# Top.net
KiCad netlist of a schematic drawn in Altium Designer
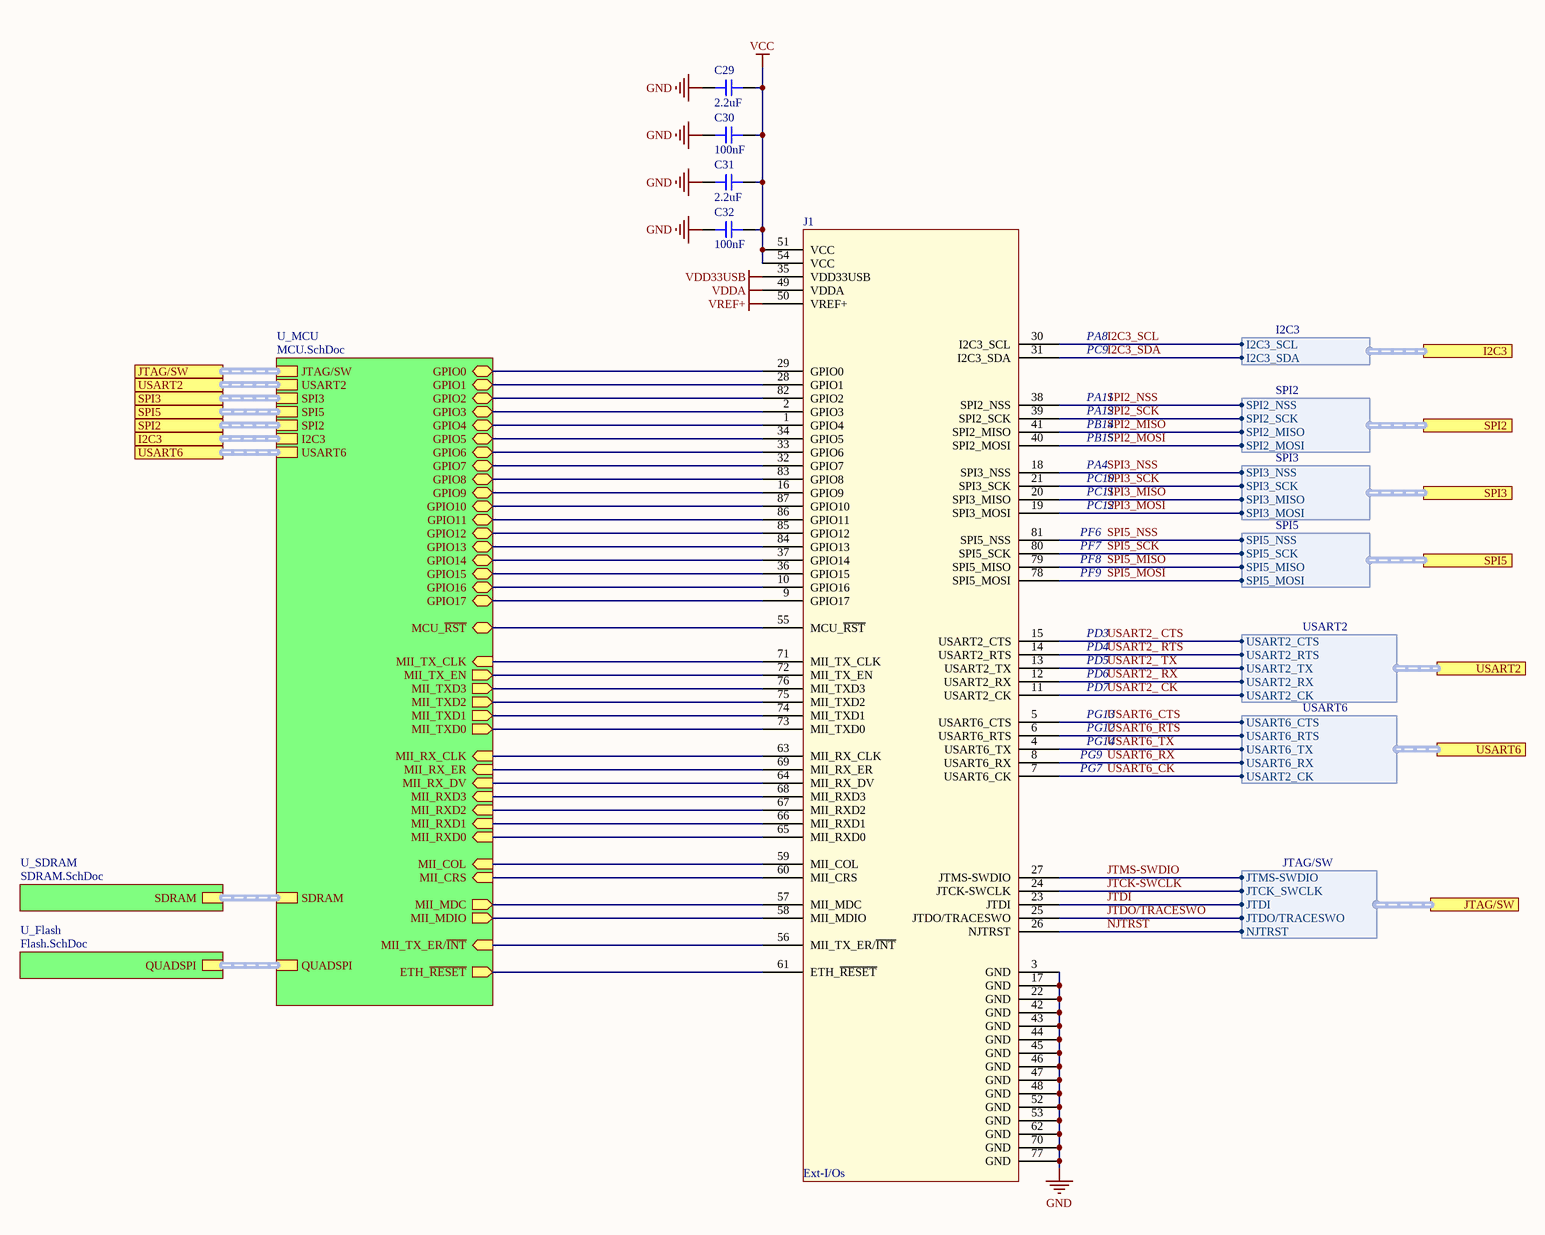
[diagram p0: Top.SchDoc]

(export (version "E")
  (design (tool "Eeschema 10.0.6"))
  (components
    (comp (ref "C29")
      (value "2.2uF")
      (footprint "Capacitor-0603")
      (fields (field (name "Comment") "C-2.2uF-0603"))
      (libsource (lib "Components") (part "C-2.2uF-0603"))
    )
    (comp (ref "C30")
      (value "100nF")
      (footprint "Capacitor-0603")
      (fields (field (name "Comment") "C-100nF-0603"))
      (libsource (lib "Components") (part "C-100nF-0603"))
    )
    (comp (ref "C31")
      (value "2.2uF")
      (footprint "Capacitor-0603")
      (fields (field (name "Comment") "C-2.2uF-0603"))
      (libsource (lib "Components") (part "C-2.2uF-0603"))
    )
    (comp (ref "C32")
      (value "100nF")
      (footprint "Capacitor-0603")
      (fields (field (name "Comment") "C-100nF-0603"))
      (libsource (lib "Components") (part "C-100nF-0603"))
    )
    (comp (ref "J1")
      (value "Ext-I/Os")
      (footprint "EXT_IOS")
      (libsource (lib "Components") (part "Ext-I/Os"))
    )
  )
  (nets
    (net (code "8") (name "/ETH_~{RESET}") (class "Default")
      (node (ref "J1") (pin "61") (pinfunction "ETH_~{RESET}_61") (pintype "passive"))
    )
    (net (code "9") (name "/GPIO0") (class "Default")
      (node (ref "J1") (pin "29") (pinfunction "GPIO0_29") (pintype "passive"))
    )
    (net (code "10") (name "/GPIO1") (class "Default")
      (node (ref "J1") (pin "28") (pinfunction "GPIO1_28") (pintype "passive"))
    )
    (net (code "11") (name "/GPIO2") (class "Default")
      (node (ref "J1") (pin "82") (pinfunction "GPIO2_82") (pintype "passive"))
    )
    (net (code "12") (name "/GPIO3") (class "Default")
      (node (ref "J1") (pin "2") (pinfunction "GPIO3_2") (pintype "passive"))
    )
    (net (code "13") (name "/GPIO4") (class "Default")
      (node (ref "J1") (pin "1") (pinfunction "GPIO4_1") (pintype "passive"))
    )
    (net (code "14") (name "/GPIO5") (class "Default")
      (node (ref "J1") (pin "34") (pinfunction "GPIO5_34") (pintype "passive"))
    )
    (net (code "15") (name "/GPIO6") (class "Default")
      (node (ref "J1") (pin "33") (pinfunction "GPIO6_33") (pintype "passive"))
    )
    (net (code "16") (name "/GPIO7") (class "Default")
      (node (ref "J1") (pin "32") (pinfunction "GPIO7_32") (pintype "passive"))
    )
    (net (code "17") (name "/GPIO8") (class "Default")
      (node (ref "J1") (pin "83") (pinfunction "GPIO8_83") (pintype "passive"))
    )
    (net (code "18") (name "/GPIO9") (class "Default")
      (node (ref "J1") (pin "16") (pinfunction "GPIO9_16") (pintype "passive"))
    )
    (net (code "19") (name "/GPIO10") (class "Default")
      (node (ref "J1") (pin "87") (pinfunction "GPIO10_87") (pintype "passive"))
    )
    (net (code "20") (name "/GPIO11") (class "Default")
      (node (ref "J1") (pin "86") (pinfunction "GPIO11_86") (pintype "passive"))
    )
    (net (code "21") (name "/GPIO12") (class "Default")
      (node (ref "J1") (pin "85") (pinfunction "GPIO12_85") (pintype "passive"))
    )
    (net (code "22") (name "/GPIO13") (class "Default")
      (node (ref "J1") (pin "84") (pinfunction "GPIO13_84") (pintype "passive"))
    )
    (net (code "23") (name "/GPIO14") (class "Default")
      (node (ref "J1") (pin "37") (pinfunction "GPIO14_37") (pintype "passive"))
    )
    (net (code "24") (name "/GPIO15") (class "Default")
      (node (ref "J1") (pin "36") (pinfunction "GPIO15_36") (pintype "passive"))
    )
    (net (code "25") (name "/GPIO16") (class "Default")
      (node (ref "J1") (pin "10") (pinfunction "GPIO16_10") (pintype "passive"))
    )
    (net (code "26") (name "/GPIO17") (class "Default")
      (node (ref "J1") (pin "9") (pinfunction "GPIO17_9") (pintype "passive"))
    )
    (net (code "27") (name "/I2C3_SCL") (class "Default")
      (node (ref "J1") (pin "30") (pinfunction "I2C3_SCL_30") (pintype "passive"))
    )
    (net (code "28") (name "/I2C3_SDA") (class "Default")
      (node (ref "J1") (pin "31") (pinfunction "I2C3_SDA_31") (pintype "passive"))
    )
    (net (code "29") (name "/JTCK-SWCLK") (class "Default")
      (node (ref "J1") (pin "24") (pinfunction "JTCK-SWCLK_24") (pintype "passive"))
    )
    (net (code "30") (name "/JTDI") (class "Default")
      (node (ref "J1") (pin "23") (pinfunction "JTDI_23") (pintype "passive"))
    )
    (net (code "31") (name "/JTDO{slash}TRACESWO") (class "Default")
      (node (ref "J1") (pin "25") (pinfunction "JTDO/TRACESWO_25") (pintype "passive"))
    )
    (net (code "32") (name "/JTMS-SWDIO") (class "Default")
      (node (ref "J1") (pin "27") (pinfunction "JTMS-SWDIO_27") (pintype "passive"))
    )
    (net (code "33") (name "/MCU_~{RST}") (class "Default")
      (node (ref "J1") (pin "55") (pinfunction "MCU_~{RST}_55") (pintype "passive"))
    )
    (net (code "34") (name "/MII_COL") (class "Default")
      (node (ref "J1") (pin "59") (pinfunction "MII_COL_59") (pintype "passive"))
    )
    (net (code "35") (name "/MII_CRS") (class "Default")
      (node (ref "J1") (pin "60") (pinfunction "MII_CRS_60") (pintype "passive"))
    )
    (net (code "36") (name "/MII_MDC") (class "Default")
      (node (ref "J1") (pin "57") (pinfunction "MII_MDC_57") (pintype "passive"))
    )
    (net (code "37") (name "/MII_MDIO") (class "Default")
      (node (ref "J1") (pin "58") (pinfunction "MII_MDIO_58") (pintype "passive"))
    )
    (net (code "38") (name "/MII_RXD0") (class "Default")
      (node (ref "J1") (pin "65") (pinfunction "MII_RXD0_65") (pintype "passive"))
    )
    (net (code "39") (name "/MII_RXD1") (class "Default")
      (node (ref "J1") (pin "66") (pinfunction "MII_RXD1_66") (pintype "passive"))
    )
    (net (code "40") (name "/MII_RXD2") (class "Default")
      (node (ref "J1") (pin "67") (pinfunction "MII_RXD2_67") (pintype "passive"))
    )
    (net (code "41") (name "/MII_RXD3") (class "Default")
      (node (ref "J1") (pin "68") (pinfunction "MII_RXD3_68") (pintype "passive"))
    )
    (net (code "42") (name "/MII_RX_CLK") (class "Default")
      (node (ref "J1") (pin "63") (pinfunction "MII_RX_CLK_63") (pintype "passive"))
    )
    (net (code "43") (name "/MII_RX_DV") (class "Default")
      (node (ref "J1") (pin "64") (pinfunction "MII_RX_DV_64") (pintype "passive"))
    )
    (net (code "44") (name "/MII_RX_ER") (class "Default")
      (node (ref "J1") (pin "69") (pinfunction "MII_RX_ER_69") (pintype "passive"))
    )
    (net (code "45") (name "/MII_TXD0") (class "Default")
      (node (ref "J1") (pin "73") (pinfunction "MII_TXD0_73") (pintype "passive"))
    )
    (net (code "46") (name "/MII_TXD1") (class "Default")
      (node (ref "J1") (pin "74") (pinfunction "MII_TXD1_74") (pintype "passive"))
    )
    (net (code "47") (name "/MII_TXD2") (class "Default")
      (node (ref "J1") (pin "75") (pinfunction "MII_TXD2_75") (pintype "passive"))
    )
    (net (code "48") (name "/MII_TXD3") (class "Default")
      (node (ref "J1") (pin "76") (pinfunction "MII_TXD3_76") (pintype "passive"))
    )
    (net (code "49") (name "/MII_TX_CLK") (class "Default")
      (node (ref "J1") (pin "71") (pinfunction "MII_TX_CLK_71") (pintype "passive"))
    )
    (net (code "50") (name "/MII_TX_EN") (class "Default")
      (node (ref "J1") (pin "72") (pinfunction "MII_TX_EN_72") (pintype "passive"))
    )
    (net (code "51") (name "/MII_TX_ER{slash}~{INT}") (class "Default")
      (node (ref "J1") (pin "56") (pinfunction "MII_TX_ER/~{INT}_56") (pintype "passive"))
    )
    (net (code "52") (name "/NJTRST") (class "Default")
      (node (ref "J1") (pin "26") (pinfunction "NJTRST_26") (pintype "passive"))
    )
    (net (code "55") (name "/SPI2_MISO") (class "Default")
      (node (ref "J1") (pin "41") (pinfunction "SPI2_MISO_41") (pintype "passive"))
    )
    (net (code "56") (name "/SPI2_MOSI") (class "Default")
      (node (ref "J1") (pin "40") (pinfunction "SPI2_MOSI_40") (pintype "passive"))
    )
    (net (code "57") (name "/SPI2_NSS") (class "Default")
      (node (ref "J1") (pin "38") (pinfunction "SPI2_NSS_38") (pintype "passive"))
    )
    (net (code "58") (name "/SPI2_SCK") (class "Default")
      (node (ref "J1") (pin "39") (pinfunction "SPI2_SCK_39") (pintype "passive"))
    )
    (net (code "59") (name "/SPI3_MISO") (class "Default")
      (node (ref "J1") (pin "20") (pinfunction "SPI3_MISO_20") (pintype "passive"))
    )
    (net (code "60") (name "/SPI3_MOSI") (class "Default")
      (node (ref "J1") (pin "19") (pinfunction "SPI3_MOSI_19") (pintype "passive"))
    )
    (net (code "61") (name "/SPI3_NSS") (class "Default")
      (node (ref "J1") (pin "18") (pinfunction "SPI3_NSS_18") (pintype "passive"))
    )
    (net (code "62") (name "/SPI3_SCK") (class "Default")
      (node (ref "J1") (pin "21") (pinfunction "SPI3_SCK_21") (pintype "passive"))
    )
    (net (code "63") (name "/SPI5_MISO") (class "Default")
      (node (ref "J1") (pin "79") (pinfunction "SPI5_MISO_79") (pintype "passive"))
    )
    (net (code "64") (name "/SPI5_MOSI") (class "Default")
      (node (ref "J1") (pin "78") (pinfunction "SPI5_MOSI_78") (pintype "passive"))
    )
    (net (code "65") (name "/SPI5_NSS") (class "Default")
      (node (ref "J1") (pin "81") (pinfunction "SPI5_NSS_81") (pintype "passive"))
    )
    (net (code "66") (name "/SPI5_SCK") (class "Default")
      (node (ref "J1") (pin "80") (pinfunction "SPI5_SCK_80") (pintype "passive"))
    )
    (net (code "67") (name "/USART2_ CK") (class "Default")
      (node (ref "J1") (pin "11") (pinfunction "USART2_CK_11") (pintype "passive"))
    )
    (net (code "68") (name "/USART2_ CTS") (class "Default")
      (node (ref "J1") (pin "15") (pinfunction "USART2_CTS_15") (pintype "passive"))
    )
    (net (code "69") (name "/USART2_ RTS") (class "Default")
      (node (ref "J1") (pin "14") (pinfunction "USART2_RTS_14") (pintype "passive"))
    )
    (net (code "70") (name "/USART2_ RX") (class "Default")
      (node (ref "J1") (pin "12") (pinfunction "USART2_RX_12") (pintype "passive"))
    )
    (net (code "71") (name "/USART2_ TX") (class "Default")
      (node (ref "J1") (pin "13") (pinfunction "USART2_TX_13") (pintype "passive"))
    )
    (net (code "72") (name "/USART6_CK") (class "Default")
      (node (ref "J1") (pin "7") (pinfunction "USART6_CK_7") (pintype "passive"))
    )
    (net (code "73") (name "/USART6_CTS") (class "Default")
      (node (ref "J1") (pin "5") (pinfunction "USART6_CTS_5") (pintype "passive"))
    )
    (net (code "74") (name "/USART6_RTS") (class "Default")
      (node (ref "J1") (pin "6") (pinfunction "USART6_RTS_6") (pintype "passive"))
    )
    (net (code "75") (name "/USART6_RX") (class "Default")
      (node (ref "J1") (pin "8") (pinfunction "USART6_RX_8") (pintype "passive"))
    )
    (net (code "76") (name "/USART6_TX") (class "Default")
      (node (ref "J1") (pin "4") (pinfunction "USART6_TX_4") (pintype "passive"))
    )
    (net (code "84") (name "GND") (class "Default")
      (node (ref "C29") (pin "1") (pinfunction "1_1") (pintype "passive"))
      (node (ref "C30") (pin "1") (pinfunction "1_1") (pintype "passive"))
      (node (ref "C31") (pin "1") (pinfunction "1_1") (pintype "passive"))
      (node (ref "C32") (pin "1") (pinfunction "1_1") (pintype "passive"))
      (node (ref "J1") (pin "17") (pinfunction "GND_17") (pintype "passive"))
      (node (ref "J1") (pin "22") (pinfunction "GND_22") (pintype "passive"))
      (node (ref "J1") (pin "3") (pinfunction "GND_3") (pintype "passive"))
      (node (ref "J1") (pin "42") (pinfunction "GND_42") (pintype "passive"))
      (node (ref "J1") (pin "43") (pinfunction "GND_43") (pintype "passive"))
      (node (ref "J1") (pin "44") (pinfunction "GND_44") (pintype "passive"))
      (node (ref "J1") (pin "45") (pinfunction "GND_45") (pintype "passive"))
      (node (ref "J1") (pin "46") (pinfunction "GND_46") (pintype "passive"))
      (node (ref "J1") (pin "47") (pinfunction "GND_47") (pintype "passive"))
      (node (ref "J1") (pin "48") (pinfunction "GND_48") (pintype "passive"))
      (node (ref "J1") (pin "52") (pinfunction "GND_52") (pintype "passive"))
      (node (ref "J1") (pin "53") (pinfunction "GND_53") (pintype "passive"))
      (node (ref "J1") (pin "62") (pinfunction "GND_62") (pintype "passive"))
      (node (ref "J1") (pin "70") (pinfunction "GND_70") (pintype "passive"))
      (node (ref "J1") (pin "77") (pinfunction "GND_77") (pintype "passive"))
    )
    (net (code "85") (name "VCC") (class "Default")
      (node (ref "C29") (pin "2") (pinfunction "2_2") (pintype "passive"))
      (node (ref "C30") (pin "2") (pinfunction "2_2") (pintype "passive"))
      (node (ref "C31") (pin "2") (pinfunction "2_2") (pintype "passive"))
      (node (ref "C32") (pin "2") (pinfunction "2_2") (pintype "passive"))
      (node (ref "J1") (pin "51") (pinfunction "VCC_51") (pintype "passive"))
      (node (ref "J1") (pin "54") (pinfunction "VCC_54") (pintype "passive"))
    )
    (net (code "86") (name "VDD33USB") (class "Default")
      (node (ref "J1") (pin "35") (pinfunction "VDD33USB_35") (pintype "passive"))
    )
    (net (code "87") (name "VDDA") (class "Default")
      (node (ref "J1") (pin "49") (pinfunction "VDDA_49") (pintype "passive"))
    )
    (net (code "88") (name "VREF+") (class "Default")
      (node (ref "J1") (pin "50") (pinfunction "VREF+_50") (pintype "passive"))
    )
  )
)
